# cpu_board.net
KiCad netlist of a schematic drawn in EAGLE
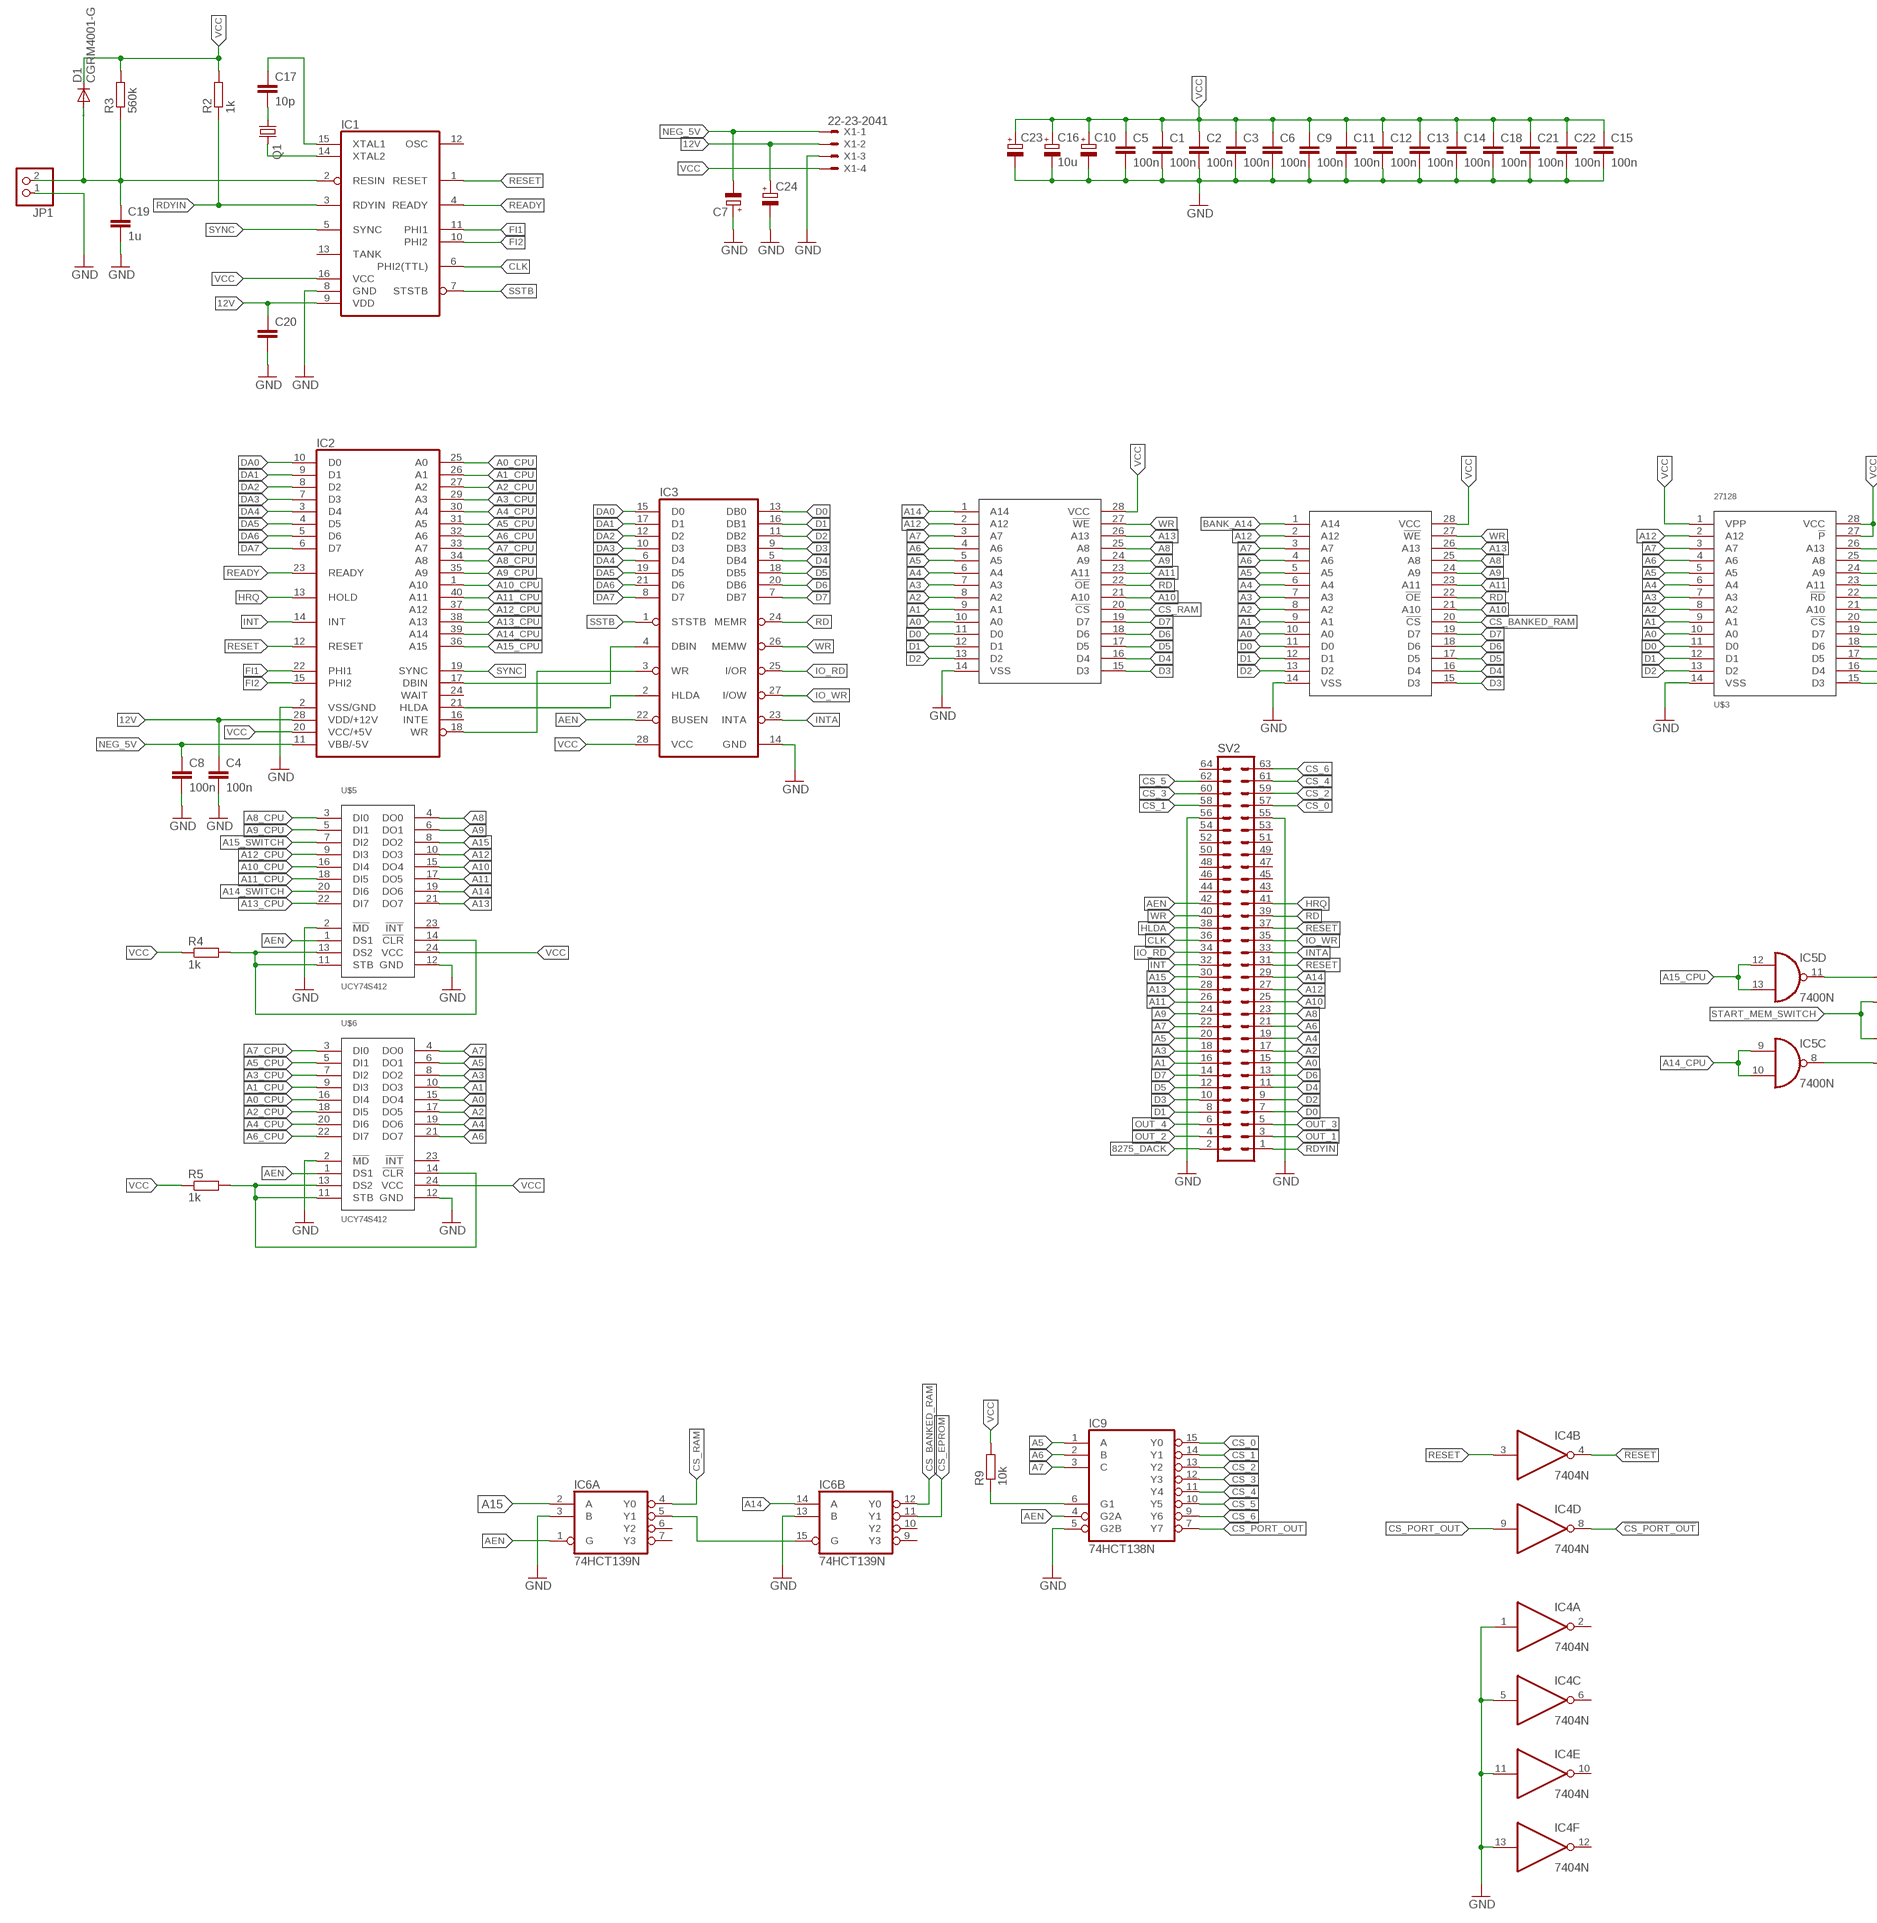
[diagram p0: schematic, sheet 1, part 1 of 2]
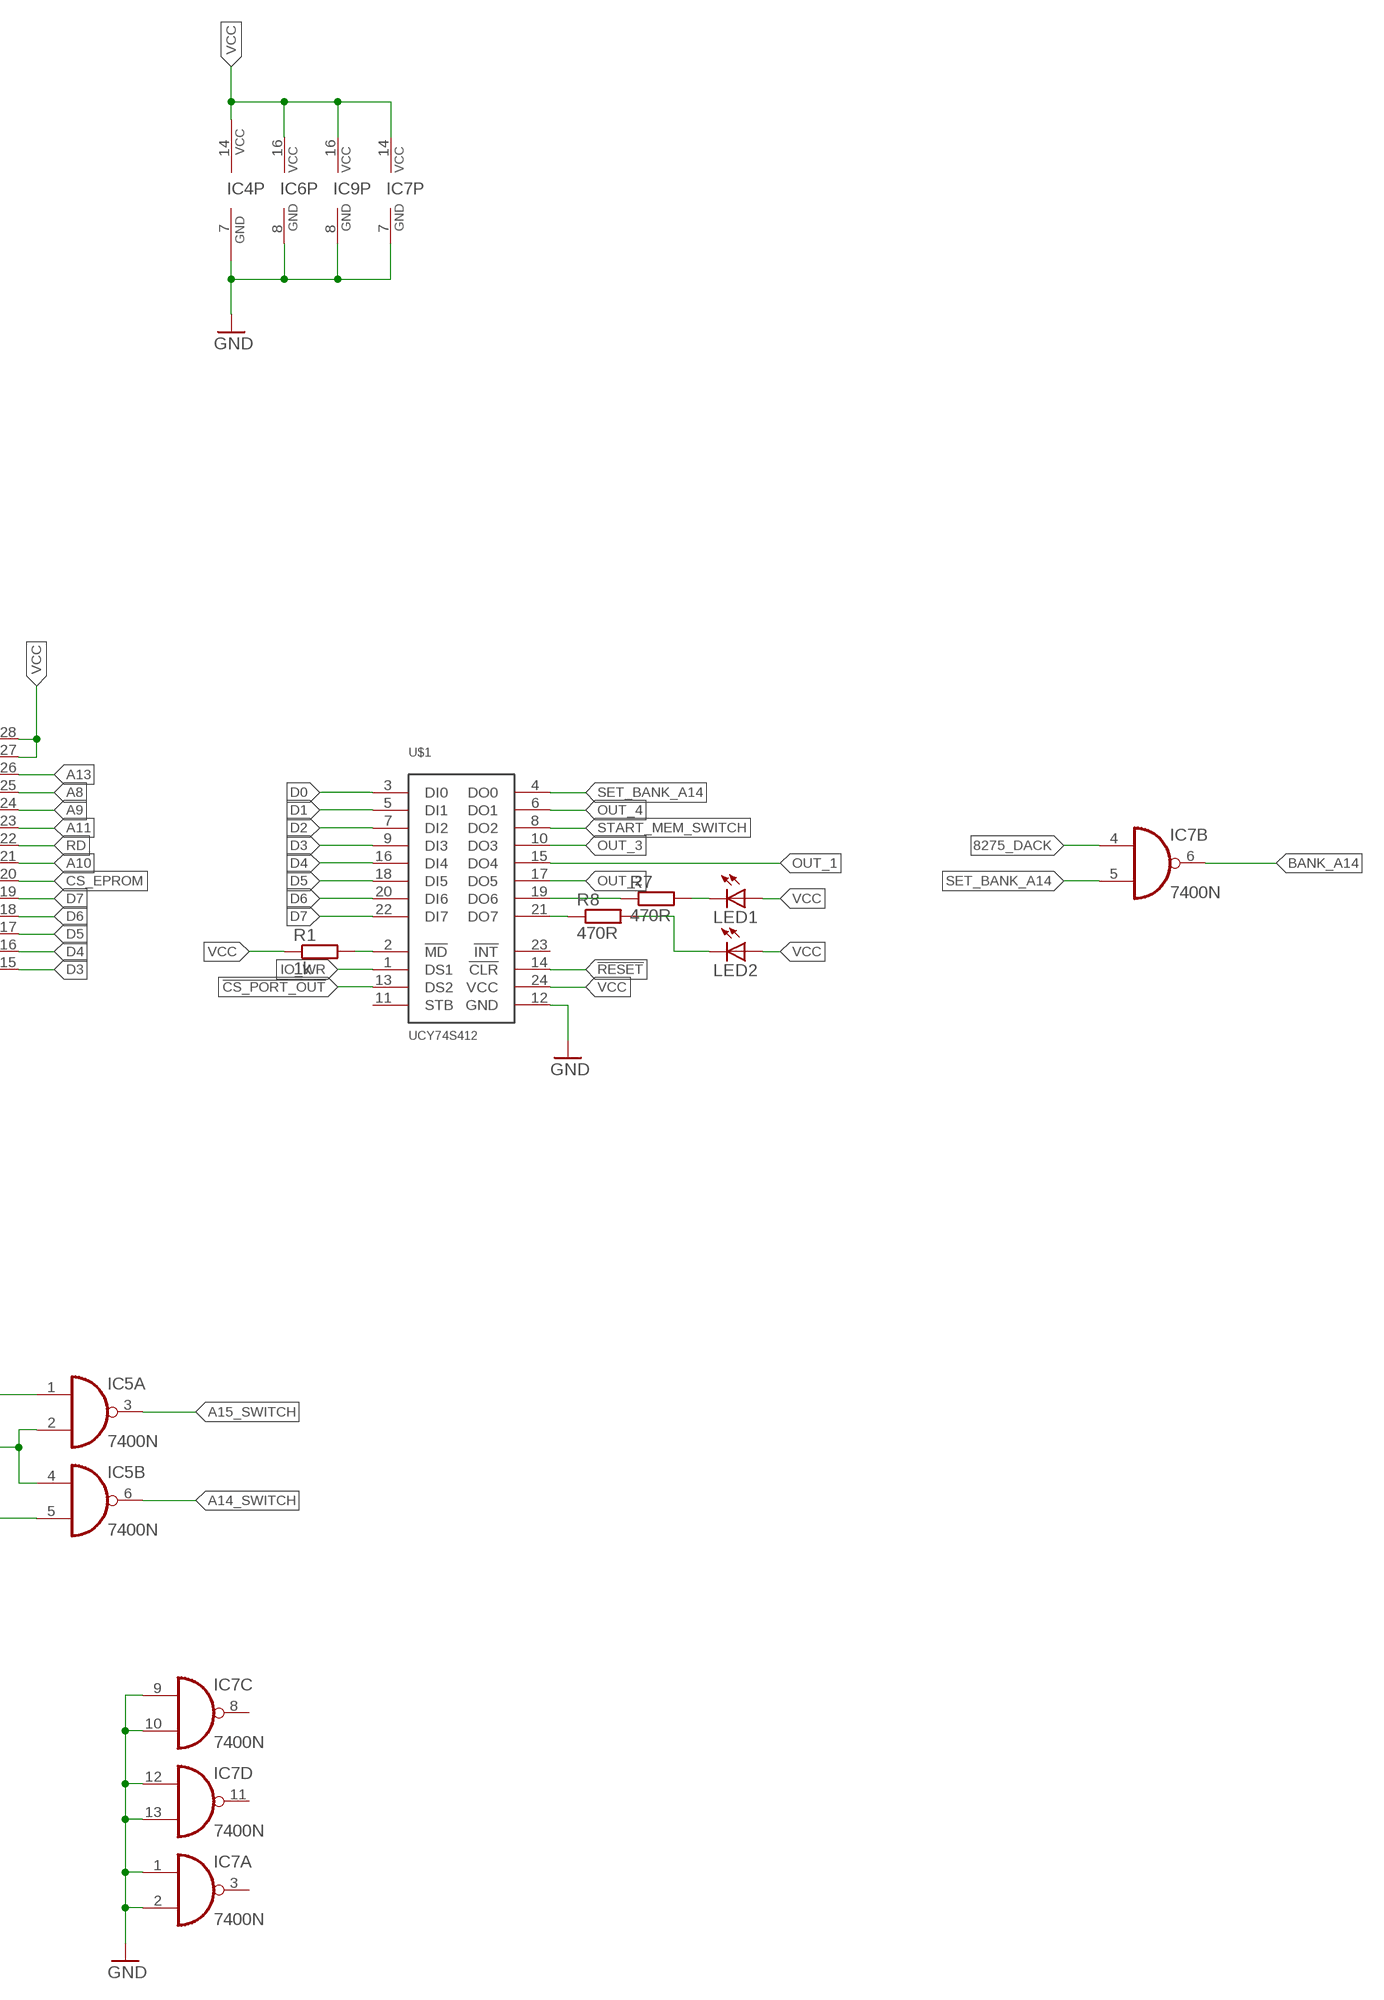
[diagram p1: schematic, sheet 1, part 2 of 2]

(export (version "E")
  (design (tool "Eeschema 10.0.6"))
  (components
    (comp (ref "C1")
      (value "100n")
      (footprint "eagle-import:C1206")
      (libsource (lib "eagle-import") (part "C-EUC1206"))
    )
    (comp (ref "C2")
      (value "100n")
      (footprint "eagle-import:C1206")
      (libsource (lib "eagle-import") (part "C-EUC1206"))
    )
    (comp (ref "C3")
      (value "100n")
      (footprint "eagle-import:C1206")
      (libsource (lib "eagle-import") (part "C-EUC1206"))
    )
    (comp (ref "C4")
      (value "100n")
      (footprint "eagle-import:C1206")
      (libsource (lib "eagle-import") (part "C-EUC1206"))
    )
    (comp (ref "C5")
      (value "100n")
      (footprint "eagle-import:C0603")
      (libsource (lib "eagle-import") (part "C-EUC0603"))
    )
    (comp (ref "C6")
      (value "100n")
      (footprint "eagle-import:C1206")
      (libsource (lib "eagle-import") (part "C-EUC1206"))
    )
    (comp (ref "C7")
      (value "CPOL-EUE2.5-7")
      (footprint "eagle-import:E2,5-7")
      (libsource (lib "eagle-import") (part "CPOL-EUE2.5-7"))
    )
    (comp (ref "C8")
      (value "100n")
      (footprint "eagle-import:C1206")
      (libsource (lib "eagle-import") (part "C-EUC1206"))
    )
    (comp (ref "C9")
      (value "100n")
      (footprint "eagle-import:C1206")
      (libsource (lib "eagle-import") (part "C-EUC1206"))
    )
    (comp (ref "C10")
      (value "CPOL-EUE5-10.5")
      (footprint "eagle-import:E5-10,5")
      (libsource (lib "eagle-import") (part "CPOL-EUE5-10.5"))
    )
    (comp (ref "C11")
      (value "100n")
      (footprint "eagle-import:C0805")
      (libsource (lib "eagle-import") (part "C-EUC0805"))
    )
    (comp (ref "C12")
      (value "100n")
      (footprint "eagle-import:C0805")
      (libsource (lib "eagle-import") (part "C-EUC0805"))
    )
    (comp (ref "C13")
      (value "100n")
      (footprint "eagle-import:C0805")
      (libsource (lib "eagle-import") (part "C-EUC0805"))
    )
    (comp (ref "C14")
      (value "100n")
      (footprint "eagle-import:C1206")
      (libsource (lib "eagle-import") (part "C-EUC1206"))
    )
    (comp (ref "C15")
      (value "100n")
      (footprint "eagle-import:C1206")
      (libsource (lib "eagle-import") (part "C-EUC1206"))
    )
    (comp (ref "C16")
      (value "10u")
      (footprint "eagle-import:SMC_B")
      (libsource (lib "eagle-import") (part "CPOL-EUSMCB"))
    )
    (comp (ref "C17")
      (value "10p")
      (footprint "eagle-import:C0603")
      (libsource (lib "eagle-import") (part "C-EUC0603"))
    )
    (comp (ref "C18")
      (value "100n")
      (footprint "eagle-import:C0603")
      (libsource (lib "eagle-import") (part "C-EUC0603"))
    )
    (comp (ref "C19")
      (value "1u")
      (footprint "eagle-import:C0603")
      (libsource (lib "eagle-import") (part "C-EUC0603"))
    )
    (comp (ref "C20")
      (value "C-EUC0603")
      (footprint "eagle-import:C0603")
      (libsource (lib "eagle-import") (part "C-EUC0603"))
    )
    (comp (ref "C21")
      (value "100n")
      (footprint "eagle-import:C1206")
      (libsource (lib "eagle-import") (part "C-EUC1206"))
    )
    (comp (ref "C22")
      (value "100n")
      (footprint "eagle-import:C0603")
      (libsource (lib "eagle-import") (part "C-EUC0603"))
    )
    (comp (ref "C23")
      (value "CPOL-EUE5-10.5")
      (footprint "eagle-import:E5-10,5")
      (libsource (lib "eagle-import") (part "CPOL-EUE5-10.5"))
    )
    (comp (ref "C24")
      (value "CPOL-EUE3.5-8")
      (footprint "eagle-import:E3,5-8")
      (libsource (lib "eagle-import") (part "CPOL-EUE3.5-8"))
    )
    (comp (ref "D1")
      (value "CGRM4001-G")
      (footprint "eagle-import:SOD-123_MINI-SMA")
      (libsource (lib "eagle-import") (part "CGRM400-G1"))
    )
    (comp (ref "IC1")
      (value "8224")
      (footprint "eagle-import:DIL16")
      (libsource (lib "eagle-import") (part "8224"))
    )
    (comp (ref "IC2")
      (value "8080")
      (footprint "eagle-import:DIL40")
      (libsource (lib "eagle-import") (part "8080"))
    )
    (comp (ref "IC3")
      (value "8228")
      (footprint "eagle-import:DIL28-6")
      (libsource (lib "eagle-import") (part "8228"))
    )
    (comp (ref "IC4")
      (value "7404N")
      (footprint "eagle-import:DIL14")
      (libsource (lib "eagle-import") (part "7404N"))
    )
    (comp (ref "IC5")
      (value "7400N")
      (footprint "eagle-import:DIL14")
      (libsource (lib "eagle-import") (part "7400N"))
    )
    (comp (ref "IC6")
      (value "74HCT139N")
      (footprint "eagle-import:DIL16")
      (libsource (lib "eagle-import") (part "74139NHCT"))
    )
    (comp (ref "IC7")
      (value "7400N")
      (footprint "eagle-import:DIL14")
      (libsource (lib "eagle-import") (part "7400N"))
    )
    (comp (ref "IC9")
      (value "74HCT138N")
      (footprint "eagle-import:DIL16")
      (libsource (lib "eagle-import") (part "74138NHCT"))
    )
    (comp (ref "JP1")
      (value "PINHD-1X2")
      (footprint "eagle-import:1X02")
      (libsource (lib "eagle-import") (part "PINHD-1X2"))
    )
    (comp (ref "LED1")
      (value "LED3MM")
      (footprint "eagle-import:LED3MM")
      (libsource (lib "eagle-import") (part "LED3MM"))
    )
    (comp (ref "LED2")
      (value "LED3MM")
      (footprint "eagle-import:LED3MM")
      (libsource (lib "eagle-import") (part "LED3MM"))
    )
    (comp (ref "Q1")
      (value "CRYSTALHC49U-V")
      (footprint "eagle-import:HC49U-V")
      (libsource (lib "eagle-import") (part "CRYSTALHC49U-V"))
    )
    (comp (ref "R1")
      (value "1k")
      (footprint "eagle-import:M1206")
      (libsource (lib "eagle-import") (part "R-EU_M1206"))
    )
    (comp (ref "R2")
      (value "1k")
      (footprint "eagle-import:R0603")
      (libsource (lib "eagle-import") (part "R-EU_R0603"))
    )
    (comp (ref "R3")
      (value "560k")
      (footprint "eagle-import:R0603")
      (libsource (lib "eagle-import") (part "R-EU_R0603"))
    )
    (comp (ref "R4")
      (value "1k")
      (footprint "eagle-import:R0603")
      (libsource (lib "eagle-import") (part "R-EU_R0603"))
    )
    (comp (ref "R5")
      (value "1k")
      (footprint "eagle-import:0204_7")
      (libsource (lib "eagle-import") (part "R-EU_0204/7"))
    )
    (comp (ref "R7")
      (value "470R")
      (footprint "eagle-import:R0603")
      (libsource (lib "eagle-import") (part "R-EU_R0603"))
    )
    (comp (ref "R8")
      (value "470R")
      (footprint "eagle-import:R0603")
      (libsource (lib "eagle-import") (part "R-EU_R0603"))
    )
    (comp (ref "R9")
      (value "10k")
      (footprint "eagle-import:R0603")
      (libsource (lib "eagle-import") (part "R-EU_R0603"))
    )
    (comp (ref "SV2")
      (value "ML64L")
      (footprint "eagle-import:ML64L")
      (libsource (lib "eagle-import") (part "ML64L"))
    )
    (comp (ref "U$1")
      (value "UCY74S412")
      (footprint "eagle-import:DIL24-6")
      (libsource (lib "eagle-import") (part "UCY74S412"))
    )
    (comp (ref "U$2")
      (value "62256")
      (footprint "eagle-import:DIL28-6")
      (libsource (lib "eagle-import") (part "62256"))
    )
    (comp (ref "U$3")
      (value "27128")
      (footprint "eagle-import:DIL28")
      (libsource (lib "eagle-import") (part "27128"))
    )
    (comp (ref "U$4")
      (value "62256")
      (footprint "eagle-import:DIL28-6")
      (libsource (lib "eagle-import") (part "62256"))
    )
    (comp (ref "U$5")
      (value "UCY74S412")
      (footprint "eagle-import:DIL24-6")
      (libsource (lib "eagle-import") (part "UCY74S412"))
    )
    (comp (ref "U$6")
      (value "UCY74S412")
      (footprint "eagle-import:DIL24-6")
      (libsource (lib "eagle-import") (part "UCY74S412"))
    )
    (comp (ref "X1")
      (value "22-23-2041")
      (footprint "eagle-import:22-23-2041")
      (fields (field (name "MF") "MOLEX"))
      (libsource (lib "eagle-import") (part "22-23-2041"))
    )
  )
  (nets
    (net (code "1") (name "/~{CS_PORT_OUT}") (class "Default")
      (node (ref "IC4") (pin "8") (pinfunction "O_8") (pintype "output"))
      (node (ref "U$1") (pin "13") (pinfunction "DS2_13") (pintype "bidirectional"))
    )
    (net (code "2") (name "/~{RESET}") (class "Default")
      (node (ref "IC4") (pin "4") (pinfunction "O_4") (pintype "output"))
      (node (ref "SV2") (pin "37") (pinfunction "37_37") (pintype "passive"))
      (node (ref "U$1") (pin "14") (pinfunction "~{CLR}_14") (pintype "bidirectional"))
    )
    (net (code "3") (name "12V") (class "Default")
      (node (ref "C20") (pin "1") (pinfunction "1_1") (pintype "passive"))
      (node (ref "C24") (pin "+") (pinfunction "+_+") (pintype "passive"))
      (node (ref "C4") (pin "1") (pinfunction "1_1") (pintype "passive"))
      (node (ref "IC1") (pin "9") (pinfunction "VDD_9") (pintype "power_in"))
      (node (ref "IC2") (pin "28") (pinfunction "VDD/+12V_28") (pintype "power_in"))
      (node (ref "X1") (pin "2") (pinfunction "S_2") (pintype "passive"))
    )
    (net (code "4") (name "8275_DACK") (class "Default")
      (node (ref "IC7") (pin "4") (pinfunction "I0_4") (pintype "input"))
      (node (ref "SV2") (pin "2") (pinfunction "2_2") (pintype "passive"))
    )
    (net (code "5") (name "A0") (class "Default")
      (node (ref "SV2") (pin "15") (pinfunction "15_15") (pintype "passive"))
      (node (ref "U$2") (pin "10") (pinfunction "A0_10") (pintype "bidirectional"))
      (node (ref "U$3") (pin "10") (pinfunction "A0_10") (pintype "bidirectional"))
      (node (ref "U$4") (pin "10") (pinfunction "A0_10") (pintype "bidirectional"))
      (node (ref "U$6") (pin "15") (pinfunction "DO4_15") (pintype "bidirectional"))
    )
    (net (code "6") (name "A0_CPU") (class "Default")
      (node (ref "IC2") (pin "25") (pinfunction "A0_25") (pintype "output"))
      (node (ref "U$6") (pin "16") (pinfunction "DI4_16") (pintype "bidirectional"))
    )
    (net (code "7") (name "A1") (class "Default")
      (node (ref "SV2") (pin "16") (pinfunction "16_16") (pintype "passive"))
      (node (ref "U$2") (pin "9") (pinfunction "A1_9") (pintype "bidirectional"))
      (node (ref "U$3") (pin "9") (pinfunction "A1_9") (pintype "bidirectional"))
      (node (ref "U$4") (pin "9") (pinfunction "A1_9") (pintype "bidirectional"))
      (node (ref "U$6") (pin "10") (pinfunction "DO3_10") (pintype "bidirectional"))
    )
    (net (code "8") (name "A1_CPU") (class "Default")
      (node (ref "IC2") (pin "26") (pinfunction "A1_26") (pintype "output"))
      (node (ref "U$6") (pin "9") (pinfunction "DI3_9") (pintype "bidirectional"))
    )
    (net (code "9") (name "A2") (class "Default")
      (node (ref "SV2") (pin "17") (pinfunction "17_17") (pintype "passive"))
      (node (ref "U$2") (pin "8") (pinfunction "A2_8") (pintype "bidirectional"))
      (node (ref "U$3") (pin "8") (pinfunction "A2_8") (pintype "bidirectional"))
      (node (ref "U$4") (pin "8") (pinfunction "A2_8") (pintype "bidirectional"))
      (node (ref "U$6") (pin "17") (pinfunction "DO5_17") (pintype "bidirectional"))
    )
    (net (code "10") (name "A2_CPU") (class "Default")
      (node (ref "IC2") (pin "27") (pinfunction "A2_27") (pintype "output"))
      (node (ref "U$6") (pin "18") (pinfunction "DI5_18") (pintype "bidirectional"))
    )
    (net (code "11") (name "A3") (class "Default")
      (node (ref "SV2") (pin "18") (pinfunction "18_18") (pintype "passive"))
      (node (ref "U$2") (pin "7") (pinfunction "A3_7") (pintype "bidirectional"))
      (node (ref "U$3") (pin "7") (pinfunction "A3_7") (pintype "bidirectional"))
      (node (ref "U$4") (pin "7") (pinfunction "A3_7") (pintype "bidirectional"))
      (node (ref "U$6") (pin "8") (pinfunction "DO2_8") (pintype "bidirectional"))
    )
    (net (code "12") (name "A3_CPU") (class "Default")
      (node (ref "IC2") (pin "29") (pinfunction "A3_29") (pintype "output"))
      (node (ref "U$6") (pin "7") (pinfunction "DI2_7") (pintype "bidirectional"))
    )
    (net (code "13") (name "A4") (class "Default")
      (node (ref "SV2") (pin "19") (pinfunction "19_19") (pintype "passive"))
      (node (ref "U$2") (pin "6") (pinfunction "A4_6") (pintype "bidirectional"))
      (node (ref "U$3") (pin "6") (pinfunction "A4_6") (pintype "bidirectional"))
      (node (ref "U$4") (pin "6") (pinfunction "A4_6") (pintype "bidirectional"))
      (node (ref "U$6") (pin "19") (pinfunction "DO6_19") (pintype "bidirectional"))
    )
    (net (code "14") (name "A4_CPU") (class "Default")
      (node (ref "IC2") (pin "30") (pinfunction "A4_30") (pintype "output"))
      (node (ref "U$6") (pin "20") (pinfunction "DI6_20") (pintype "bidirectional"))
    )
    (net (code "15") (name "A5") (class "Default")
      (node (ref "IC9") (pin "1") (pinfunction "A_1") (pintype "input"))
      (node (ref "SV2") (pin "20") (pinfunction "20_20") (pintype "passive"))
      (node (ref "U$2") (pin "5") (pinfunction "A5_5") (pintype "bidirectional"))
      (node (ref "U$3") (pin "5") (pinfunction "A5_5") (pintype "bidirectional"))
      (node (ref "U$4") (pin "5") (pinfunction "A5_5") (pintype "bidirectional"))
      (node (ref "U$6") (pin "6") (pinfunction "DO1_6") (pintype "bidirectional"))
    )
    (net (code "16") (name "A5_CPU") (class "Default")
      (node (ref "IC2") (pin "31") (pinfunction "A5_31") (pintype "output"))
      (node (ref "U$6") (pin "5") (pinfunction "DI1_5") (pintype "bidirectional"))
    )
    (net (code "17") (name "A6") (class "Default")
      (node (ref "IC9") (pin "2") (pinfunction "B_2") (pintype "input"))
      (node (ref "SV2") (pin "21") (pinfunction "21_21") (pintype "passive"))
      (node (ref "U$2") (pin "4") (pinfunction "A6_4") (pintype "bidirectional"))
      (node (ref "U$3") (pin "4") (pinfunction "A6_4") (pintype "bidirectional"))
      (node (ref "U$4") (pin "4") (pinfunction "A6_4") (pintype "bidirectional"))
      (node (ref "U$6") (pin "21") (pinfunction "DO7_21") (pintype "bidirectional"))
    )
    (net (code "18") (name "A6_CPU") (class "Default")
      (node (ref "IC2") (pin "32") (pinfunction "A6_32") (pintype "output"))
      (node (ref "U$6") (pin "22") (pinfunction "DI7_22") (pintype "bidirectional"))
    )
    (net (code "19") (name "A7") (class "Default")
      (node (ref "IC9") (pin "3") (pinfunction "C_3") (pintype "input"))
      (node (ref "SV2") (pin "22") (pinfunction "22_22") (pintype "passive"))
      (node (ref "U$2") (pin "3") (pinfunction "A7_3") (pintype "bidirectional"))
      (node (ref "U$3") (pin "3") (pinfunction "A7_3") (pintype "bidirectional"))
      (node (ref "U$4") (pin "3") (pinfunction "A7_3") (pintype "bidirectional"))
      (node (ref "U$6") (pin "4") (pinfunction "DO0_4") (pintype "bidirectional"))
    )
    (net (code "20") (name "A7_CPU") (class "Default")
      (node (ref "IC2") (pin "33") (pinfunction "A7_33") (pintype "output"))
      (node (ref "U$6") (pin "3") (pinfunction "DI0_3") (pintype "bidirectional"))
    )
    (net (code "21") (name "A8") (class "Default")
      (node (ref "SV2") (pin "23") (pinfunction "23_23") (pintype "passive"))
      (node (ref "U$2") (pin "25") (pinfunction "A8_25") (pintype "bidirectional"))
      (node (ref "U$3") (pin "25") (pinfunction "A8_25") (pintype "bidirectional"))
      (node (ref "U$4") (pin "25") (pinfunction "A8_25") (pintype "bidirectional"))
      (node (ref "U$5") (pin "4") (pinfunction "DO0_4") (pintype "bidirectional"))
    )
    (net (code "22") (name "A8_CPU") (class "Default")
      (node (ref "IC2") (pin "34") (pinfunction "A8_34") (pintype "output"))
      (node (ref "U$5") (pin "3") (pinfunction "DI0_3") (pintype "bidirectional"))
    )
    (net (code "23") (name "A9") (class "Default")
      (node (ref "SV2") (pin "24") (pinfunction "24_24") (pintype "passive"))
      (node (ref "U$2") (pin "24") (pinfunction "A9_24") (pintype "bidirectional"))
      (node (ref "U$3") (pin "24") (pinfunction "A9_24") (pintype "bidirectional"))
      (node (ref "U$4") (pin "24") (pinfunction "A9_24") (pintype "bidirectional"))
      (node (ref "U$5") (pin "6") (pinfunction "DO1_6") (pintype "bidirectional"))
    )
    (net (code "24") (name "A9_CPU") (class "Default")
      (node (ref "IC2") (pin "35") (pinfunction "A9_35") (pintype "output"))
      (node (ref "U$5") (pin "5") (pinfunction "DI1_5") (pintype "bidirectional"))
    )
    (net (code "25") (name "A10") (class "Default")
      (node (ref "SV2") (pin "25") (pinfunction "25_25") (pintype "passive"))
      (node (ref "U$2") (pin "21") (pinfunction "A10_21") (pintype "bidirectional"))
      (node (ref "U$3") (pin "21") (pinfunction "A10_21") (pintype "bidirectional"))
      (node (ref "U$4") (pin "21") (pinfunction "A10_21") (pintype "bidirectional"))
      (node (ref "U$5") (pin "15") (pinfunction "DO4_15") (pintype "bidirectional"))
    )
    (net (code "26") (name "A10_CPU") (class "Default")
      (node (ref "IC2") (pin "1") (pinfunction "A10_1") (pintype "output"))
      (node (ref "U$5") (pin "16") (pinfunction "DI4_16") (pintype "bidirectional"))
    )
    (net (code "27") (name "A11") (class "Default")
      (node (ref "SV2") (pin "26") (pinfunction "26_26") (pintype "passive"))
      (node (ref "U$2") (pin "23") (pinfunction "A11_23") (pintype "bidirectional"))
      (node (ref "U$3") (pin "23") (pinfunction "A11_23") (pintype "bidirectional"))
      (node (ref "U$4") (pin "23") (pinfunction "A11_23") (pintype "bidirectional"))
      (node (ref "U$5") (pin "17") (pinfunction "DO5_17") (pintype "bidirectional"))
    )
    (net (code "28") (name "A11_CPU") (class "Default")
      (node (ref "IC2") (pin "40") (pinfunction "A11_40") (pintype "output"))
      (node (ref "U$5") (pin "18") (pinfunction "DI5_18") (pintype "bidirectional"))
    )
    (net (code "29") (name "A12") (class "Default")
      (node (ref "SV2") (pin "27") (pinfunction "27_27") (pintype "passive"))
      (node (ref "U$2") (pin "2") (pinfunction "A12_2") (pintype "bidirectional"))
      (node (ref "U$3") (pin "2") (pinfunction "A12_2") (pintype "bidirectional"))
      (node (ref "U$4") (pin "2") (pinfunction "A12_2") (pintype "bidirectional"))
      (node (ref "U$5") (pin "10") (pinfunction "DO3_10") (pintype "bidirectional"))
    )
    (net (code "30") (name "A12_CPU") (class "Default")
      (node (ref "IC2") (pin "37") (pinfunction "A12_37") (pintype "output"))
      (node (ref "U$5") (pin "9") (pinfunction "DI3_9") (pintype "bidirectional"))
    )
    (net (code "31") (name "A13") (class "Default")
      (node (ref "SV2") (pin "28") (pinfunction "28_28") (pintype "passive"))
      (node (ref "U$2") (pin "26") (pinfunction "A13_26") (pintype "bidirectional"))
      (node (ref "U$3") (pin "26") (pinfunction "A13_26") (pintype "bidirectional"))
      (node (ref "U$4") (pin "26") (pinfunction "A13_26") (pintype "bidirectional"))
      (node (ref "U$5") (pin "21") (pinfunction "DO7_21") (pintype "bidirectional"))
    )
    (net (code "32") (name "A13_CPU") (class "Default")
      (node (ref "IC2") (pin "38") (pinfunction "A13_38") (pintype "output"))
      (node (ref "U$5") (pin "22") (pinfunction "DI7_22") (pintype "bidirectional"))
    )
    (net (code "33") (name "A14") (class "Default")
      (node (ref "IC6") (pin "14") (pinfunction "A_14") (pintype "input"))
      (node (ref "SV2") (pin "29") (pinfunction "29_29") (pintype "passive"))
      (node (ref "U$4") (pin "1") (pinfunction "A14_1") (pintype "bidirectional"))
      (node (ref "U$5") (pin "19") (pinfunction "DO6_19") (pintype "bidirectional"))
    )
    (net (code "34") (name "A14_CPU") (class "Default")
      (node (ref "IC2") (pin "39") (pinfunction "A14_39") (pintype "output"))
      (node (ref "IC5") (pin "10") (pinfunction "I1_10") (pintype "input"))
      (node (ref "IC5") (pin "9") (pinfunction "I0_9") (pintype "input"))
    )
    (net (code "35") (name "A14_SWITCH") (class "Default")
      (node (ref "IC5") (pin "6") (pinfunction "O_6") (pintype "output"))
      (node (ref "U$5") (pin "20") (pinfunction "DI6_20") (pintype "bidirectional"))
    )
    (net (code "36") (name "A15") (class "Default")
      (node (ref "IC6") (pin "2") (pinfunction "A_2") (pintype "input"))
      (node (ref "SV2") (pin "30") (pinfunction "30_30") (pintype "passive"))
      (node (ref "U$5") (pin "8") (pinfunction "DO2_8") (pintype "bidirectional"))
    )
    (net (code "37") (name "A15_CPU") (class "Default")
      (node (ref "IC2") (pin "36") (pinfunction "A15_36") (pintype "output"))
      (node (ref "IC5") (pin "12") (pinfunction "I0_12") (pintype "input"))
      (node (ref "IC5") (pin "13") (pinfunction "I1_13") (pintype "input"))
    )
    (net (code "38") (name "A15_SWITCH") (class "Default")
      (node (ref "IC5") (pin "3") (pinfunction "O_3") (pintype "output"))
      (node (ref "U$5") (pin "7") (pinfunction "DI2_7") (pintype "bidirectional"))
    )
    (net (code "39") (name "AEN") (class "Default")
      (node (ref "IC3") (pin "22") (pinfunction "BUSEN_22") (pintype "input"))
      (node (ref "IC6") (pin "1") (pinfunction "G_1") (pintype "input"))
      (node (ref "IC9") (pin "4") (pinfunction "G2A_4") (pintype "input"))
      (node (ref "SV2") (pin "42") (pinfunction "42_42") (pintype "passive"))
      (node (ref "U$5") (pin "1") (pinfunction "DS1_1") (pintype "bidirectional"))
      (node (ref "U$6") (pin "1") (pinfunction "DS1_1") (pintype "bidirectional"))
    )
    (net (code "40") (name "BANK_A14") (class "Default")
      (node (ref "IC7") (pin "6") (pinfunction "O_6") (pintype "output"))
      (node (ref "U$2") (pin "1") (pinfunction "A14_1") (pintype "bidirectional"))
    )
    (net (code "41") (name "CLK") (class "Default")
      (node (ref "IC1") (pin "6") (pinfunction "PHI2(TTL)_6") (pintype "output"))
      (node (ref "SV2") (pin "36") (pinfunction "36_36") (pintype "passive"))
    )
    (net (code "42") (name "CS_0") (class "Default")
      (node (ref "IC9") (pin "15") (pinfunction "Y0_15") (pintype "output"))
      (node (ref "SV2") (pin "57") (pinfunction "57_57") (pintype "passive"))
    )
    (net (code "43") (name "CS_1") (class "Default")
      (node (ref "IC9") (pin "14") (pinfunction "Y1_14") (pintype "output"))
      (node (ref "SV2") (pin "58") (pinfunction "58_58") (pintype "passive"))
    )
    (net (code "44") (name "CS_2") (class "Default")
      (node (ref "IC9") (pin "13") (pinfunction "Y2_13") (pintype "output"))
      (node (ref "SV2") (pin "59") (pinfunction "59_59") (pintype "passive"))
    )
    (net (code "45") (name "CS_3") (class "Default")
      (node (ref "IC9") (pin "12") (pinfunction "Y3_12") (pintype "output"))
      (node (ref "SV2") (pin "60") (pinfunction "60_60") (pintype "passive"))
    )
    (net (code "46") (name "CS_4") (class "Default")
      (node (ref "IC9") (pin "11") (pinfunction "Y4_11") (pintype "output"))
      (node (ref "SV2") (pin "61") (pinfunction "61_61") (pintype "passive"))
    )
    (net (code "47") (name "CS_5") (class "Default")
      (node (ref "IC9") (pin "10") (pinfunction "Y5_10") (pintype "output"))
      (node (ref "SV2") (pin "62") (pinfunction "62_62") (pintype "passive"))
    )
    (net (code "48") (name "CS_6") (class "Default")
      (node (ref "IC9") (pin "9") (pinfunction "Y6_9") (pintype "output"))
      (node (ref "SV2") (pin "63") (pinfunction "63_63") (pintype "passive"))
    )
    (net (code "49") (name "CS_BANKED_RAM") (class "Default")
      (node (ref "IC6") (pin "12") (pinfunction "Y0_12") (pintype "output"))
      (node (ref "U$2") (pin "20") (pinfunction "~{CS}_20") (pintype "bidirectional"))
    )
    (net (code "50") (name "CS_EPROM") (class "Default")
      (node (ref "IC6") (pin "11") (pinfunction "Y1_11") (pintype "output"))
      (node (ref "U$3") (pin "20") (pinfunction "~{CS}_20") (pintype "bidirectional"))
    )
    (net (code "51") (name "CS_PORT_OUT") (class "Default")
      (node (ref "IC4") (pin "9") (pinfunction "I_9") (pintype "input"))
      (node (ref "IC9") (pin "7") (pinfunction "Y7_7") (pintype "output"))
    )
    (net (code "52") (name "CS_RAM") (class "Default")
      (node (ref "IC6") (pin "4") (pinfunction "Y0_4") (pintype "output"))
      (node (ref "U$4") (pin "20") (pinfunction "~{CS}_20") (pintype "bidirectional"))
    )
    (net (code "53") (name "D0") (class "Default")
      (node (ref "IC3") (pin "13") (pinfunction "DB0_13") (pintype "bidirectional"))
      (node (ref "SV2") (pin "7") (pinfunction "7_7") (pintype "passive"))
      (node (ref "U$1") (pin "3") (pinfunction "DI0_3") (pintype "bidirectional"))
      (node (ref "U$2") (pin "11") (pinfunction "D0_11") (pintype "bidirectional"))
      (node (ref "U$3") (pin "11") (pinfunction "D0_11") (pintype "bidirectional"))
      (node (ref "U$4") (pin "11") (pinfunction "D0_11") (pintype "bidirectional"))
    )
    (net (code "54") (name "D1") (class "Default")
      (node (ref "IC3") (pin "16") (pinfunction "DB1_16") (pintype "bidirectional"))
      (node (ref "SV2") (pin "8") (pinfunction "8_8") (pintype "passive"))
      (node (ref "U$1") (pin "5") (pinfunction "DI1_5") (pintype "bidirectional"))
      (node (ref "U$2") (pin "12") (pinfunction "D1_12") (pintype "bidirectional"))
      (node (ref "U$3") (pin "12") (pinfunction "D1_12") (pintype "bidirectional"))
      (node (ref "U$4") (pin "12") (pinfunction "D1_12") (pintype "bidirectional"))
    )
    (net (code "55") (name "D2") (class "Default")
      (node (ref "IC3") (pin "11") (pinfunction "DB2_11") (pintype "bidirectional"))
      (node (ref "SV2") (pin "9") (pinfunction "9_9") (pintype "passive"))
      (node (ref "U$1") (pin "7") (pinfunction "DI2_7") (pintype "bidirectional"))
      (node (ref "U$2") (pin "13") (pinfunction "D2_13") (pintype "bidirectional"))
      (node (ref "U$3") (pin "13") (pinfunction "D2_13") (pintype "bidirectional"))
      (node (ref "U$4") (pin "13") (pinfunction "D2_13") (pintype "bidirectional"))
    )
    (net (code "56") (name "D3") (class "Default")
      (node (ref "IC3") (pin "9") (pinfunction "DB3_9") (pintype "bidirectional"))
      (node (ref "SV2") (pin "10") (pinfunction "10_10") (pintype "passive"))
      (node (ref "U$1") (pin "9") (pinfunction "DI3_9") (pintype "bidirectional"))
      (node (ref "U$2") (pin "15") (pinfunction "D3_15") (pintype "bidirectional"))
      (node (ref "U$3") (pin "15") (pinfunction "D3_15") (pintype "bidirectional"))
      (node (ref "U$4") (pin "15") (pinfunction "D3_15") (pintype "bidirectional"))
    )
    (net (code "57") (name "D4") (class "Default")
      (node (ref "IC3") (pin "5") (pinfunction "DB4_5") (pintype "bidirectional"))
      (node (ref "SV2") (pin "11") (pinfunction "11_11") (pintype "passive"))
      (node (ref "U$1") (pin "16") (pinfunction "DI4_16") (pintype "bidirectional"))
      (node (ref "U$2") (pin "16") (pinfunction "D4_16") (pintype "bidirectional"))
      (node (ref "U$3") (pin "16") (pinfunction "D4_16") (pintype "bidirectional"))
      (node (ref "U$4") (pin "16") (pinfunction "D4_16") (pintype "bidirectional"))
    )
    (net (code "58") (name "D5") (class "Default")
      (node (ref "IC3") (pin "18") (pinfunction "DB5_18") (pintype "bidirectional"))
      (node (ref "SV2") (pin "12") (pinfunction "12_12") (pintype "passive"))
      (node (ref "U$1") (pin "18") (pinfunction "DI5_18") (pintype "bidirectional"))
      (node (ref "U$2") (pin "17") (pinfunction "D5_17") (pintype "bidirectional"))
      (node (ref "U$3") (pin "17") (pinfunction "D5_17") (pintype "bidirectional"))
      (node (ref "U$4") (pin "17") (pinfunction "D5_17") (pintype "bidirectional"))
    )
    (net (code "59") (name "D6") (class "Default")
      (node (ref "IC3") (pin "20") (pinfunction "DB6_20") (pintype "bidirectional"))
      (node (ref "SV2") (pin "13") (pinfunction "13_13") (pintype "passive"))
      (node (ref "U$1") (pin "20") (pinfunction "DI6_20") (pintype "bidirectional"))
      (node (ref "U$2") (pin "18") (pinfunction "D6_18") (pintype "bidirectional"))
      (node (ref "U$3") (pin "18") (pinfunction "D6_18") (pintype "bidirectional"))
      (node (ref "U$4") (pin "18") (pinfunction "D6_18") (pintype "bidirectional"))
    )
    (net (code "60") (name "D7") (class "Default")
      (node (ref "IC3") (pin "7") (pinfunction "DB7_7") (pintype "bidirectional"))
      (node (ref "SV2") (pin "14") (pinfunction "14_14") (pintype "passive"))
      (node (ref "U$1") (pin "22") (pinfunction "DI7_22") (pintype "bidirectional"))
      (node (ref "U$2") (pin "19") (pinfunction "D7_19") (pintype "bidirectional"))
      (node (ref "U$3") (pin "19") (pinfunction "D7_19") (pintype "bidirectional"))
      (node (ref "U$4") (pin "19") (pinfunction "D7_19") (pintype "bidirectional"))
    )
    (net (code "61") (name "DA0") (class "Default")
      (node (ref "IC2") (pin "10") (pinfunction "D0_10") (pintype "bidirectional"))
      (node (ref "IC3") (pin "15") (pinfunction "D0_15") (pintype "bidirectional"))
    )
    (net (code "62") (name "DA1") (class "Default")
      (node (ref "IC2") (pin "9") (pinfunction "D1_9") (pintype "bidirectional"))
      (node (ref "IC3") (pin "17") (pinfunction "D1_17") (pintype "bidirectional"))
    )
    (net (code "63") (name "DA2") (class "Default")
      (node (ref "IC2") (pin "8") (pinfunction "D2_8") (pintype "bidirectional"))
      (node (ref "IC3") (pin "12") (pinfunction "D2_12") (pintype "bidirectional"))
    )
    (net (code "64") (name "DA3") (class "Default")
      (node (ref "IC2") (pin "7") (pinfunction "D3_7") (pintype "bidirectional"))
      (node (ref "IC3") (pin "10") (pinfunction "D3_10") (pintype "bidirectional"))
    )
    (net (code "65") (name "DA4") (class "Default")
      (node (ref "IC2") (pin "3") (pinfunction "D4_3") (pintype "bidirectional"))
      (node (ref "IC3") (pin "6") (pinfunction "D4_6") (pintype "bidirectional"))
    )
    (net (code "66") (name "DA5") (class "Default")
      (node (ref "IC2") (pin "4") (pinfunction "D5_4") (pintype "bidirectional"))
      (node (ref "IC3") (pin "19") (pinfunction "D5_19") (pintype "bidirectional"))
    )
    (net (code "67") (name "DA6") (class "Default")
      (node (ref "IC2") (pin "5") (pinfunction "D6_5") (pintype "bidirectional"))
      (node (ref "IC3") (pin "21") (pinfunction "D6_21") (pintype "bidirectional"))
    )
    (net (code "68") (name "DA7") (class "Default")
      (node (ref "IC2") (pin "6") (pinfunction "D7_6") (pintype "bidirectional"))
      (node (ref "IC3") (pin "8") (pinfunction "D7_8") (pintype "bidirectional"))
    )
    (net (code "69") (name "FI1") (class "Default")
      (node (ref "IC1") (pin "11") (pinfunction "PHI1_11") (pintype "output"))
      (node (ref "IC2") (pin "22") (pinfunction "PHI1_22") (pintype "input"))
    )
    (net (code "70") (name "FI2") (class "Default")
      (node (ref "IC1") (pin "10") (pinfunction "PHI2_10") (pintype "output"))
      (node (ref "IC2") (pin "15") (pinfunction "PHI2_15") (pintype "input"))
    )
    (net (code "71") (name "GND") (class "Default")
      (node (ref "C1") (pin "2") (pinfunction "2_2") (pintype "passive"))
      (node (ref "C10") (pin "-") (pinfunction "-_-") (pintype "passive"))
      (node (ref "C11") (pin "2") (pinfunction "2_2") (pintype "passive"))
      (node (ref "C12") (pin "2") (pinfunction "2_2") (pintype "passive"))
      (node (ref "C13") (pin "2") (pinfunction "2_2") (pintype "passive"))
      (node (ref "C14") (pin "2") (pinfunction "2_2") (pintype "passive"))
      (node (ref "C15") (pin "2") (pinfunction "2_2") (pintype "passive"))
      (node (ref "C16") (pin "-") (pinfunction "-_-") (pintype "passive"))
      (node (ref "C18") (pin "2") (pinfunction "2_2") (pintype "passive"))
      (node (ref "C19") (pin "2") (pinfunction "2_2") (pintype "passive"))
      (node (ref "C2") (pin "2") (pinfunction "2_2") (pintype "passive"))
      (node (ref "C20") (pin "2") (pinfunction "2_2") (pintype "passive"))
      (node (ref "C21") (pin "2") (pinfunction "2_2") (pintype "passive"))
      (node (ref "C22") (pin "2") (pinfunction "2_2") (pintype "passive"))
      (node (ref "C23") (pin "-") (pinfunction "-_-") (pintype "passive"))
      (node (ref "C24") (pin "-") (pinfunction "-_-") (pintype "passive"))
      (node (ref "C3") (pin "2") (pinfunction "2_2") (pintype "passive"))
      (node (ref "C4") (pin "2") (pinfunction "2_2") (pintype "passive"))
      (node (ref "C5") (pin "2") (pinfunction "2_2") (pintype "passive"))
      (node (ref "C6") (pin "2") (pinfunction "2_2") (pintype "passive"))
      (node (ref "C7") (pin "+") (pinfunction "+_+") (pintype "passive"))
      (node (ref "C8") (pin "2") (pinfunction "2_2") (pintype "passive"))
      (node (ref "C9") (pin "2") (pinfunction "2_2") (pintype "passive"))
      (node (ref "IC1") (pin "8") (pinfunction "GND_8") (pintype "power_in"))
      (node (ref "IC2") (pin "2") (pinfunction "VSS/GND_2") (pintype "power_in"))
      (node (ref "IC3") (pin "14") (pinfunction "GND_14") (pintype "power_in"))
      (node (ref "IC4") (pin "1") (pinfunction "I_1") (pintype "input"))
      (node (ref "IC4") (pin "11") (pinfunction "I_11") (pintype "input"))
      (node (ref "IC4") (pin "13") (pinfunction "I_13") (pintype "input"))
      (node (ref "IC4") (pin "5") (pinfunction "I_5") (pintype "input"))
      (node (ref "IC4") (pin "7") (pinfunction "GND_7") (pintype "power_in"))
      (node (ref "IC6") (pin "13") (pinfunction "B_13") (pintype "input"))
      (node (ref "IC6") (pin "3") (pinfunction "B_3") (pintype "input"))
      (node (ref "IC6") (pin "8") (pinfunction "GND_8") (pintype "power_in"))
      (node (ref "IC7") (pin "1") (pinfunction "I0_1") (pintype "input"))
      (node (ref "IC7") (pin "10") (pinfunction "I1_10") (pintype "input"))
      (node (ref "IC7") (pin "12") (pinfunction "I0_12") (pintype "input"))
      (node (ref "IC7") (pin "13") (pinfunction "I1_13") (pintype "input"))
      (node (ref "IC7") (pin "2") (pinfunction "I1_2") (pintype "input"))
      (node (ref "IC7") (pin "7") (pinfunction "GND_7") (pintype "power_in"))
      (node (ref "IC7") (pin "9") (pinfunction "I0_9") (pintype "input"))
      (node (ref "IC9") (pin "5") (pinfunction "G2B_5") (pintype "input"))
      (node (ref "IC9") (pin "8") (pinfunction "GND_8") (pintype "power_in"))
      (node (ref "JP1") (pin "1") (pinfunction "1_1") (pintype "passive"))
      (node (ref "SV2") (pin "55") (pinfunction "55_55") (pintype "passive"))
      (node (ref "SV2") (pin "56") (pinfunction "56_56") (pintype "passive"))
      (node (ref "U$1") (pin "12") (pinfunction "GND_12") (pintype "bidirectional"))
      (node (ref "U$2") (pin "14") (pinfunction "VSS_14") (pintype "bidirectional"))
      (node (ref "U$3") (pin "14") (pinfunction "VSS_14") (pintype "bidirectional"))
      (node (ref "U$4") (pin "14") (pinfunction "VSS_14") (pintype "bidirectional"))
      (node (ref "U$5") (pin "12") (pinfunction "GND_12") (pintype "bidirectional"))
      (node (ref "U$5") (pin "2") (pinfunction "~{MD}_2") (pintype "bidirectional"))
      (node (ref "U$6") (pin "12") (pinfunction "GND_12") (pintype "bidirectional"))
      (node (ref "U$6") (pin "2") (pinfunction "~{MD}_2") (pintype "bidirectional"))
      (node (ref "X1") (pin "3") (pinfunction "S_3") (pintype "passive"))
    )
    (net (code "72") (name "HLDA") (class "Default")
      (node (ref "IC2") (pin "21") (pinfunction "HLDA_21") (pintype "output"))
      (node (ref "IC3") (pin "2") (pinfunction "HLDA_2") (pintype "input"))
      (node (ref "SV2") (pin "38") (pinfunction "38_38") (pintype "passive"))
    )
    (net (code "73") (name "HRQ") (class "Default")
      (node (ref "IC2") (pin "13") (pinfunction "HOLD_13") (pintype "input"))
      (node (ref "SV2") (pin "41") (pinfunction "41_41") (pintype "passive"))
    )
    (net (code "74") (name "INT") (class "Default")
      (node (ref "IC2") (pin "14") (pinfunction "INT_14") (pintype "input"))
      (node (ref "SV2") (pin "32") (pinfunction "32_32") (pintype "passive"))
    )
    (net (code "75") (name "INTA") (class "Default")
      (node (ref "IC3") (pin "23") (pinfunction "INTA_23") (pintype "output"))
      (node (ref "SV2") (pin "33") (pinfunction "33_33") (pintype "passive"))
    )
    (net (code "76") (name "IO_RD") (class "Default")
      (node (ref "IC3") (pin "25") (pinfunction "I/OR_25") (pintype "output"))
      (node (ref "SV2") (pin "34") (pinfunction "34_34") (pintype "passive"))
    )
    (net (code "77") (name "IO_WR") (class "Default")
      (node (ref "IC3") (pin "27") (pinfunction "I/OW_27") (pintype "output"))
      (node (ref "SV2") (pin "35") (pinfunction "35_35") (pintype "passive"))
      (node (ref "U$1") (pin "1") (pinfunction "DS1_1") (pintype "bidirectional"))
    )
    (net (code "78") (name "NEG_5V") (class "Default")
      (node (ref "C7") (pin "-") (pinfunction "-_-") (pintype "passive"))
      (node (ref "C8") (pin "1") (pinfunction "1_1") (pintype "passive"))
      (node (ref "IC2") (pin "11") (pinfunction "VBB/-5V_11") (pintype "power_in"))
      (node (ref "X1") (pin "1") (pinfunction "S_1") (pintype "passive"))
    )
    (net (code "79") (name "Net-(C17-Pad2)") (class "Default")
      (node (ref "C17") (pin "2") (pinfunction "2_2") (pintype "passive"))
      (node (ref "Q1") (pin "1") (pinfunction "1_1") (pintype "passive"))
    )
    (net (code "80") (name "Net-(IC1-RESIN)") (class "Default")
      (node (ref "C19") (pin "1") (pinfunction "1_1") (pintype "passive"))
      (node (ref "D1") (pin "A") (pinfunction "A_A") (pintype "passive"))
      (node (ref "IC1") (pin "2") (pinfunction "RESIN_2") (pintype "input"))
      (node (ref "JP1") (pin "2") (pinfunction "2_2") (pintype "passive"))
      (node (ref "R3") (pin "1") (pinfunction "1_1") (pintype "passive"))
    )
    (net (code "81") (name "Net-(IC1-XTAL1)") (class "Default")
      (node (ref "C17") (pin "1") (pinfunction "1_1") (pintype "passive"))
      (node (ref "IC1") (pin "15") (pinfunction "XTAL1_15") (pintype "input"))
    )
    (net (code "82") (name "Net-(IC1-XTAL2)") (class "Default")
      (node (ref "IC1") (pin "14") (pinfunction "XTAL2_14") (pintype "input"))
      (node (ref "Q1") (pin "2") (pinfunction "2_2") (pintype "passive"))
    )
    (net (code "83") (name "Net-(IC2-DBIN)") (class "Default")
      (node (ref "IC2") (pin "17") (pinfunction "DBIN_17") (pintype "output"))
      (node (ref "IC3") (pin "4") (pinfunction "DBIN_4") (pintype "input"))
    )
    (net (code "84") (name "Net-(IC2-WR)") (class "Default")
      (node (ref "IC2") (pin "18") (pinfunction "WR_18") (pintype "output"))
      (node (ref "IC3") (pin "3") (pinfunction "WR_3") (pintype "input"))
    )
    (net (code "85") (name "Net-(IC5A-I0)") (class "Default")
      (node (ref "IC5") (pin "1") (pinfunction "I0_1") (pintype "input"))
      (node (ref "IC5") (pin "11") (pinfunction "O_11") (pintype "output"))
    )
    (net (code "86") (name "Net-(IC5B-I1)") (class "Default")
      (node (ref "IC5") (pin "5") (pinfunction "I1_5") (pintype "input"))
      (node (ref "IC5") (pin "8") (pinfunction "O_8") (pintype "output"))
    )
    (net (code "87") (name "Net-(IC6A-Y1)") (class "Default")
      (node (ref "IC6") (pin "15") (pinfunction "G_15") (pintype "input"))
      (node (ref "IC6") (pin "5") (pinfunction "Y1_5") (pintype "output"))
    )
    (net (code "88") (name "Net-(IC9A-G1)") (class "Default")
      (node (ref "IC9") (pin "6") (pinfunction "G1_6") (pintype "input"))
      (node (ref "R9") (pin "1") (pinfunction "1_1") (pintype "passive"))
    )
    (net (code "89") (name "Net-(LED1-C)") (class "Default")
      (node (ref "LED1") (pin "K") (pinfunction "C_K") (pintype "passive"))
      (node (ref "R7") (pin "2") (pinfunction "2_2") (pintype "passive"))
    )
    (net (code "90") (name "Net-(LED2-C)") (class "Default")
      (node (ref "LED2") (pin "K") (pinfunction "C_K") (pintype "passive"))
      (node (ref "R8") (pin "2") (pinfunction "2_2") (pintype "passive"))
    )
    (net (code "91") (name "Net-(U$1-DO6)") (class "Default")
      (node (ref "R7") (pin "1") (pinfunction "1_1") (pintype "passive"))
      (node (ref "U$1") (pin "19") (pinfunction "DO6_19") (pintype "bidirectional"))
    )
    (net (code "92") (name "Net-(U$1-DO7)") (class "Default")
      (node (ref "R8") (pin "1") (pinfunction "1_1") (pintype "passive"))
      (node (ref "U$1") (pin "21") (pinfunction "DO7_21") (pintype "bidirectional"))
    )
    (net (code "93") (name "Net-(U$1-~{MD})") (class "Default")
      (node (ref "R1") (pin "2") (pinfunction "2_2") (pintype "passive"))
      (node (ref "U$1") (pin "2") (pinfunction "~{MD}_2") (pintype "bidirectional"))
    )
    (net (code "94") (name "Net-(U$5-DS2)") (class "Default")
      (node (ref "R4") (pin "2") (pinfunction "2_2") (pintype "passive"))
      (node (ref "U$5") (pin "11") (pinfunction "STB_11") (pintype "bidirectional"))
      (node (ref "U$5") (pin "13") (pinfunction "DS2_13") (pintype "bidirectional"))
      (node (ref "U$5") (pin "14") (pinfunction "~{CLR}_14") (pintype "bidirectional"))
    )
    (net (code "95") (name "Net-(U$6-DS2)") (class "Default")
      (node (ref "R5") (pin "2") (pinfunction "2_2") (pintype "passive"))
      (node (ref "U$6") (pin "11") (pinfunction "STB_11") (pintype "bidirectional"))
      (node (ref "U$6") (pin "13") (pinfunction "DS2_13") (pintype "bidirectional"))
      (node (ref "U$6") (pin "14") (pinfunction "~{CLR}_14") (pintype "bidirectional"))
    )
    (net (code "96") (name "OUT_1") (class "Default")
      (node (ref "SV2") (pin "3") (pinfunction "3_3") (pintype "passive"))
      (node (ref "U$1") (pin "15") (pinfunction "DO4_15") (pintype "bidirectional"))
    )
    (net (code "97") (name "OUT_2") (class "Default")
      (node (ref "SV2") (pin "4") (pinfunction "4_4") (pintype "passive"))
      (node (ref "U$1") (pin "17") (pinfunction "DO5_17") (pintype "bidirectional"))
    )
    (net (code "98") (name "OUT_3") (class "Default")
      (node (ref "SV2") (pin "5") (pinfunction "5_5") (pintype "passive"))
      (node (ref "U$1") (pin "10") (pinfunction "DO3_10") (pintype "bidirectional"))
    )
    (net (code "99") (name "OUT_4") (class "Default")
      (node (ref "SV2") (pin "6") (pinfunction "6_6") (pintype "passive"))
      (node (ref "U$1") (pin "6") (pinfunction "DO1_6") (pintype "bidirectional"))
    )
    (net (code "100") (name "RD") (class "Default")
      (node (ref "IC3") (pin "24") (pinfunction "MEMR_24") (pintype "output"))
      (node (ref "SV2") (pin "39") (pinfunction "39_39") (pintype "passive"))
      (node (ref "U$2") (pin "22") (pinfunction "~{OE}_22") (pintype "bidirectional"))
      (node (ref "U$3") (pin "22") (pinfunction "~{RD}_22") (pintype "bidirectional"))
      (node (ref "U$4") (pin "22") (pinfunction "~{OE}_22") (pintype "bidirectional"))
    )
    (net (code "101") (name "RDYIN") (class "Default")
      (node (ref "IC1") (pin "3") (pinfunction "RDYIN_3") (pintype "input"))
      (node (ref "R2") (pin "1") (pinfunction "1_1") (pintype "passive"))
      (node (ref "SV2") (pin "1") (pinfunction "1_1") (pintype "passive"))
    )
    (net (code "102") (name "READY") (class "Default")
      (node (ref "IC1") (pin "4") (pinfunction "READY_4") (pintype "output"))
      (node (ref "IC2") (pin "23") (pinfunction "READY_23") (pintype "input"))
    )
    (net (code "103") (name "RESET") (class "Default")
      (node (ref "IC1") (pin "1") (pinfunction "RESET_1") (pintype "output"))
      (node (ref "IC2") (pin "12") (pinfunction "RESET_12") (pintype "input"))
      (node (ref "IC4") (pin "3") (pinfunction "I_3") (pintype "input"))
      (node (ref "SV2") (pin "31") (pinfunction "31_31") (pintype "passive"))
    )
    (net (code "104") (name "SET_BANK_A14") (class "Default")
      (node (ref "IC7") (pin "5") (pinfunction "I1_5") (pintype "input"))
      (node (ref "U$1") (pin "4") (pinfunction "DO0_4") (pintype "bidirectional"))
    )
    (net (code "105") (name "SSTB") (class "Default")
      (node (ref "IC1") (pin "7") (pinfunction "STSTB_7") (pintype "output"))
      (node (ref "IC3") (pin "1") (pinfunction "STSTB_1") (pintype "input"))
    )
    (net (code "106") (name "START_MEM_SWITCH") (class "Default")
      (node (ref "IC5") (pin "2") (pinfunction "I1_2") (pintype "input"))
      (node (ref "IC5") (pin "4") (pinfunction "I0_4") (pintype "input"))
      (node (ref "U$1") (pin "8") (pinfunction "DO2_8") (pintype "bidirectional"))
    )
    (net (code "107") (name "SYNC") (class "Default")
      (node (ref "IC1") (pin "5") (pinfunction "SYNC_5") (pintype "input"))
      (node (ref "IC2") (pin "19") (pinfunction "SYNC_19") (pintype "output"))
    )
    (net (code "108") (name "VCC") (class "Default")
      (node (ref "C1") (pin "1") (pinfunction "1_1") (pintype "passive"))
      (node (ref "C10") (pin "+") (pinfunction "+_+") (pintype "passive"))
      (node (ref "C11") (pin "1") (pinfunction "1_1") (pintype "passive"))
      (node (ref "C12") (pin "1") (pinfunction "1_1") (pintype "passive"))
      (node (ref "C13") (pin "1") (pinfunction "1_1") (pintype "passive"))
      (node (ref "C14") (pin "1") (pinfunction "1_1") (pintype "passive"))
      (node (ref "C15") (pin "1") (pinfunction "1_1") (pintype "passive"))
      (node (ref "C16") (pin "+") (pinfunction "+_+") (pintype "passive"))
      (node (ref "C18") (pin "1") (pinfunction "1_1") (pintype "passive"))
      (node (ref "C2") (pin "1") (pinfunction "1_1") (pintype "passive"))
      (node (ref "C21") (pin "1") (pinfunction "1_1") (pintype "passive"))
      (node (ref "C22") (pin "1") (pinfunction "1_1") (pintype "passive"))
      (node (ref "C23") (pin "+") (pinfunction "+_+") (pintype "passive"))
      (node (ref "C3") (pin "1") (pinfunction "1_1") (pintype "passive"))
      (node (ref "C5") (pin "1") (pinfunction "1_1") (pintype "passive"))
      (node (ref "C6") (pin "1") (pinfunction "1_1") (pintype "passive"))
      (node (ref "C9") (pin "1") (pinfunction "1_1") (pintype "passive"))
      (node (ref "D1") (pin "C") (pinfunction "C_C") (pintype "passive"))
      (node (ref "IC1") (pin "16") (pinfunction "VCC_16") (pintype "power_in"))
      (node (ref "IC2") (pin "20") (pinfunction "VCC/+5V_20") (pintype "power_in"))
      (node (ref "IC3") (pin "28") (pinfunction "VCC_28") (pintype "power_in"))
      (node (ref "IC4") (pin "14") (pinfunction "VCC_14") (pintype "power_in"))
      (node (ref "IC6") (pin "16") (pinfunction "VCC_16") (pintype "power_in"))
      (node (ref "IC7") (pin "14") (pinfunction "VCC_14") (pintype "power_in"))
      (node (ref "IC9") (pin "16") (pinfunction "VCC_16") (pintype "power_in"))
      (node (ref "LED1") (pin "A") (pinfunction "A_A") (pintype "passive"))
      (node (ref "LED2") (pin "A") (pinfunction "A_A") (pintype "passive"))
      (node (ref "R1") (pin "1") (pinfunction "1_1") (pintype "passive"))
      (node (ref "R2") (pin "2") (pinfunction "2_2") (pintype "passive"))
      (node (ref "R3") (pin "2") (pinfunction "2_2") (pintype "passive"))
      (node (ref "R4") (pin "1") (pinfunction "1_1") (pintype "passive"))
      (node (ref "R5") (pin "1") (pinfunction "1_1") (pintype "passive"))
      (node (ref "R9") (pin "2") (pinfunction "2_2") (pintype "passive"))
      (node (ref "U$1") (pin "24") (pinfunction "VCC_24") (pintype "bidirectional"))
      (node (ref "U$2") (pin "28") (pinfunction "VCC_28") (pintype "bidirectional"))
      (node (ref "U$3") (pin "1") (pinfunction "VPP_1") (pintype "bidirectional"))
      (node (ref "U$3") (pin "27") (pinfunction "~{P}_27") (pintype "bidirectional"))
      (node (ref "U$3") (pin "28") (pinfunction "VCC_28") (pintype "bidirectional"))
      (node (ref "U$4") (pin "28") (pinfunction "VCC_28") (pintype "bidirectional"))
      (node (ref "U$5") (pin "24") (pinfunction "VCC_24") (pintype "bidirectional"))
      (node (ref "U$6") (pin "24") (pinfunction "VCC_24") (pintype "bidirectional"))
      (node (ref "X1") (pin "4") (pinfunction "S_4") (pintype "passive"))
    )
    (net (code "109") (name "WR") (class "Default")
      (node (ref "IC3") (pin "26") (pinfunction "MEMW_26") (pintype "output"))
      (node (ref "SV2") (pin "40") (pinfunction "40_40") (pintype "passive"))
      (node (ref "U$2") (pin "27") (pinfunction "~{WE}_27") (pintype "bidirectional"))
      (node (ref "U$4") (pin "27") (pinfunction "~{WE}_27") (pintype "bidirectional"))
    )
    (net (code "110") (name "unconnected-(IC1-OSC-Pad12)") (class "Default")
      (node (ref "IC1") (pin "12") (pinfunction "OSC_12") (pintype "output"))
    )
    (net (code "111") (name "unconnected-(IC1-TANK-Pad13)") (class "Default")
      (node (ref "IC1") (pin "13") (pinfunction "TANK_13") (pintype "input"))
    )
    (net (code "112") (name "unconnected-(IC2-INTE-Pad16)") (class "Default")
      (node (ref "IC2") (pin "16") (pinfunction "INTE_16") (pintype "output"))
    )
    (net (code "113") (name "unconnected-(IC2-WAIT-Pad24)") (class "Default")
      (node (ref "IC2") (pin "24") (pinfunction "WAIT_24") (pintype "output"))
    )
    (net (code "114") (name "unconnected-(IC4A-O-Pad2)") (class "Default")
      (node (ref "IC4") (pin "2") (pinfunction "O_2") (pintype "output"))
    )
    (net (code "115") (name "unconnected-(IC4C-O-Pad6)") (class "Default")
      (node (ref "IC4") (pin "6") (pinfunction "O_6") (pintype "output"))
    )
    (net (code "116") (name "unconnected-(IC4E-O-Pad10)") (class "Default")
      (node (ref "IC4") (pin "10") (pinfunction "O_10") (pintype "output"))
    )
    (net (code "117") (name "unconnected-(IC4F-O-Pad12)") (class "Default")
      (node (ref "IC4") (pin "12") (pinfunction "O_12") (pintype "output"))
    )
    (net (code "118") (name "unconnected-(IC6A-Y2-Pad6)") (class "Default")
      (node (ref "IC6") (pin "6") (pinfunction "Y2_6") (pintype "output"))
    )
    (net (code "119") (name "unconnected-(IC6A-Y3-Pad7)") (class "Default")
      (node (ref "IC6") (pin "7") (pinfunction "Y3_7") (pintype "output"))
    )
    (net (code "120") (name "unconnected-(IC6B-Y2-Pad10)") (class "Default")
      (node (ref "IC6") (pin "10") (pinfunction "Y2_10") (pintype "output"))
    )
    (net (code "121") (name "unconnected-(IC6B-Y3-Pad9)") (class "Default")
      (node (ref "IC6") (pin "9") (pinfunction "Y3_9") (pintype "output"))
    )
    (net (code "122") (name "unconnected-(IC7A-O-Pad3)") (class "Default")
      (node (ref "IC7") (pin "3") (pinfunction "O_3") (pintype "output"))
    )
    (net (code "123") (name "unconnected-(IC7C-O-Pad8)") (class "Default")
      (node (ref "IC7") (pin "8") (pinfunction "O_8") (pintype "output"))
    )
    (net (code "124") (name "unconnected-(IC7D-O-Pad11)") (class "Default")
      (node (ref "IC7") (pin "11") (pinfunction "O_11") (pintype "output"))
    )
    (net (code "125") (name "unconnected-(SV2-Pad43)") (class "Default")
      (node (ref "SV2") (pin "43") (pinfunction "43_43") (pintype "passive"))
    )
    (net (code "126") (name "unconnected-(SV2-Pad44)") (class "Default")
      (node (ref "SV2") (pin "44") (pinfunction "44_44") (pintype "passive"))
    )
    (net (code "127") (name "unconnected-(SV2-Pad45)") (class "Default")
      (node (ref "SV2") (pin "45") (pinfunction "45_45") (pintype "passive"))
    )
    (net (code "128") (name "unconnected-(SV2-Pad46)") (class "Default")
      (node (ref "SV2") (pin "46") (pinfunction "46_46") (pintype "passive"))
    )
    (net (code "129") (name "unconnected-(SV2-Pad47)") (class "Default")
      (node (ref "SV2") (pin "47") (pinfunction "47_47") (pintype "passive"))
    )
    (net (code "130") (name "unconnected-(SV2-Pad48)") (class "Default")
      (node (ref "SV2") (pin "48") (pinfunction "48_48") (pintype "passive"))
    )
    (net (code "131") (name "unconnected-(SV2-Pad49)") (class "Default")
      (node (ref "SV2") (pin "49") (pinfunction "49_49") (pintype "passive"))
    )
    (net (code "132") (name "unconnected-(SV2-Pad50)") (class "Default")
      (node (ref "SV2") (pin "50") (pinfunction "50_50") (pintype "passive"))
    )
    (net (code "133") (name "unconnected-(SV2-Pad51)") (class "Default")
      (node (ref "SV2") (pin "51") (pinfunction "51_51") (pintype "passive"))
    )
    (net (code "134") (name "unconnected-(SV2-Pad52)") (class "Default")
      (node (ref "SV2") (pin "52") (pinfunction "52_52") (pintype "passive"))
    )
    (net (code "135") (name "unconnected-(SV2-Pad53)") (class "Default")
      (node (ref "SV2") (pin "53") (pinfunction "53_53") (pintype "passive"))
    )
    (net (code "136") (name "unconnected-(SV2-Pad54)") (class "Default")
      (node (ref "SV2") (pin "54") (pinfunction "54_54") (pintype "passive"))
    )
    (net (code "137") (name "unconnected-(SV2-Pad64)") (class "Default")
      (node (ref "SV2") (pin "64") (pinfunction "64_64") (pintype "passive"))
    )
    (net (code "138") (name "unconnected-(U$1-STB-Pad11)") (class "Default")
      (node (ref "U$1") (pin "11") (pinfunction "STB_11") (pintype "bidirectional"))
    )
    (net (code "139") (name "unconnected-(U$1-~{INT}-Pad23)") (class "Default")
      (node (ref "U$1") (pin "23") (pinfunction "~{INT}_23") (pintype "bidirectional"))
    )
    (net (code "140") (name "unconnected-(U$5-~{INT}-Pad23)") (class "Default")
      (node (ref "U$5") (pin "23") (pinfunction "~{INT}_23") (pintype "bidirectional"))
    )
    (net (code "141") (name "unconnected-(U$6-~{INT}-Pad23)") (class "Default")
      (node (ref "U$6") (pin "23") (pinfunction "~{INT}_23") (pintype "bidirectional"))
    )
  )
)
